# 2014_PDU_REV-7_2_2.net
KiCad netlist of a schematic drawn in EAGLE
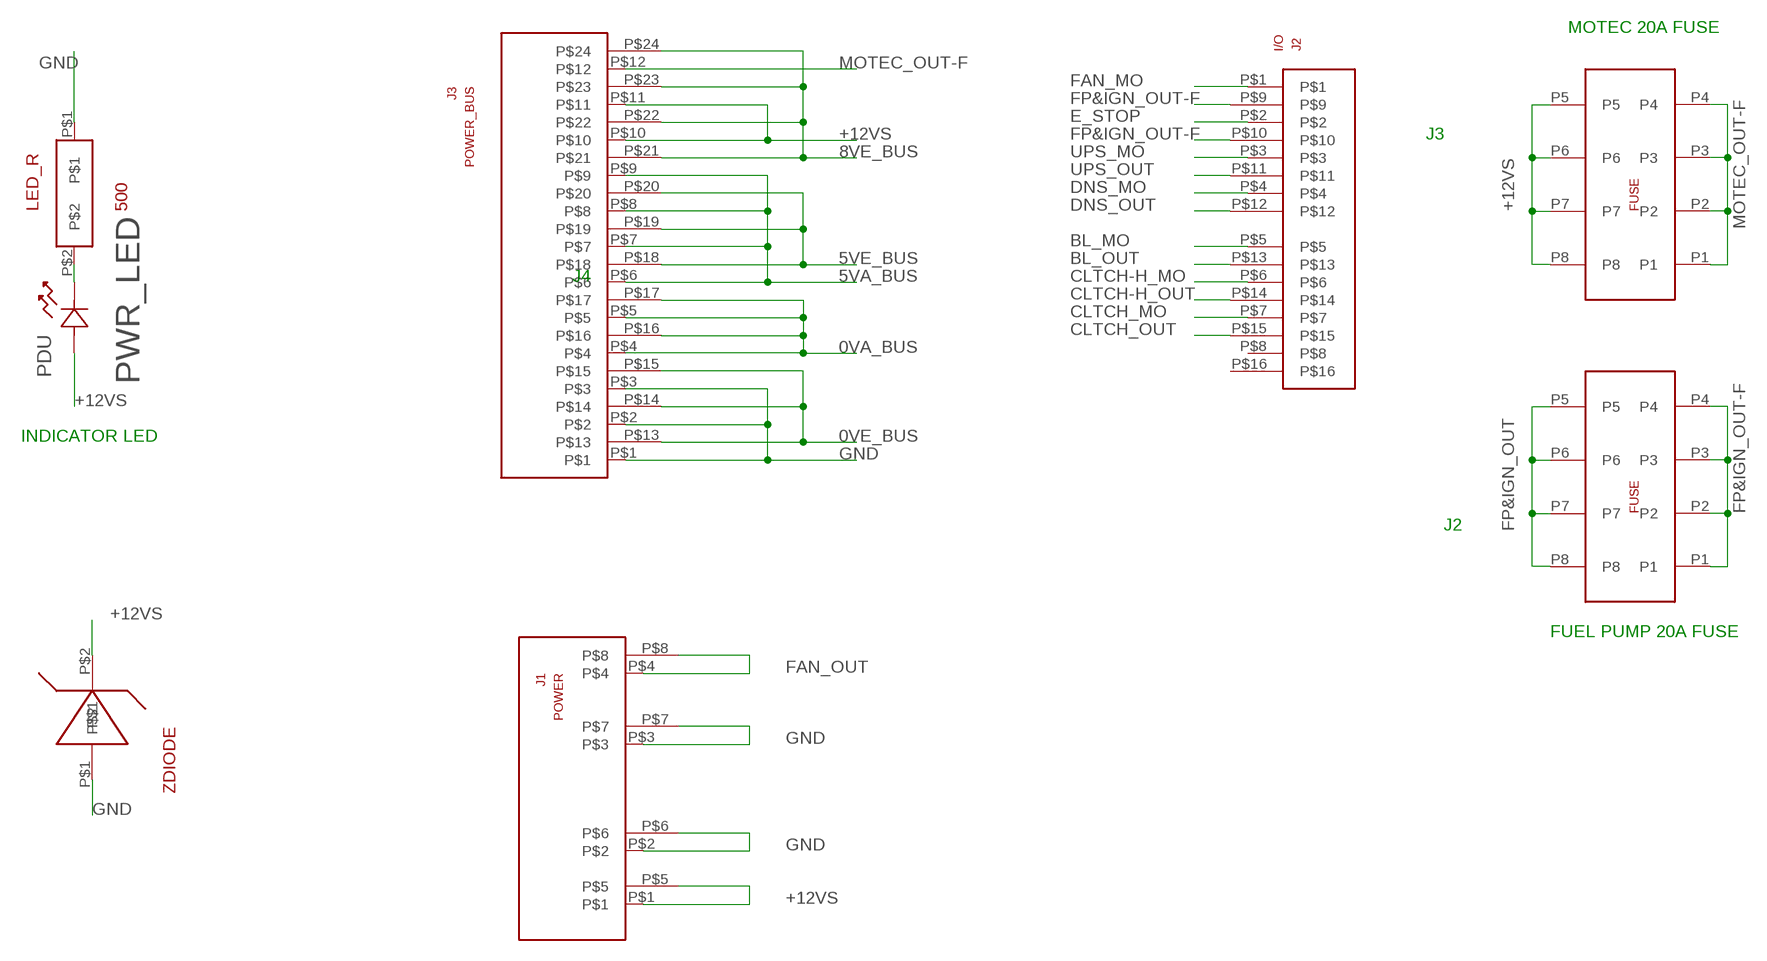
[diagram p0: schematic, sheet 1]
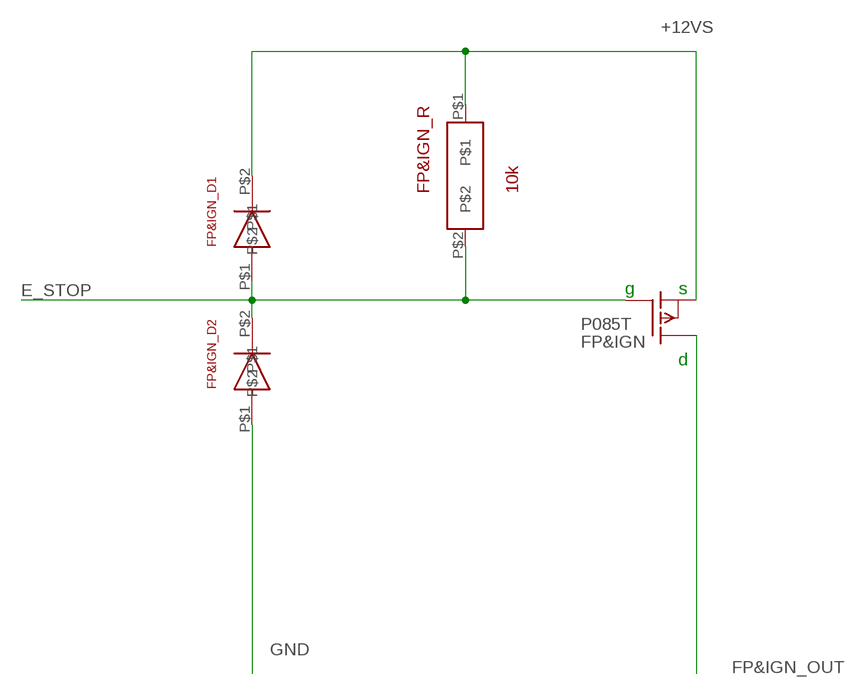
[diagram p1: schematic, sheet 2]
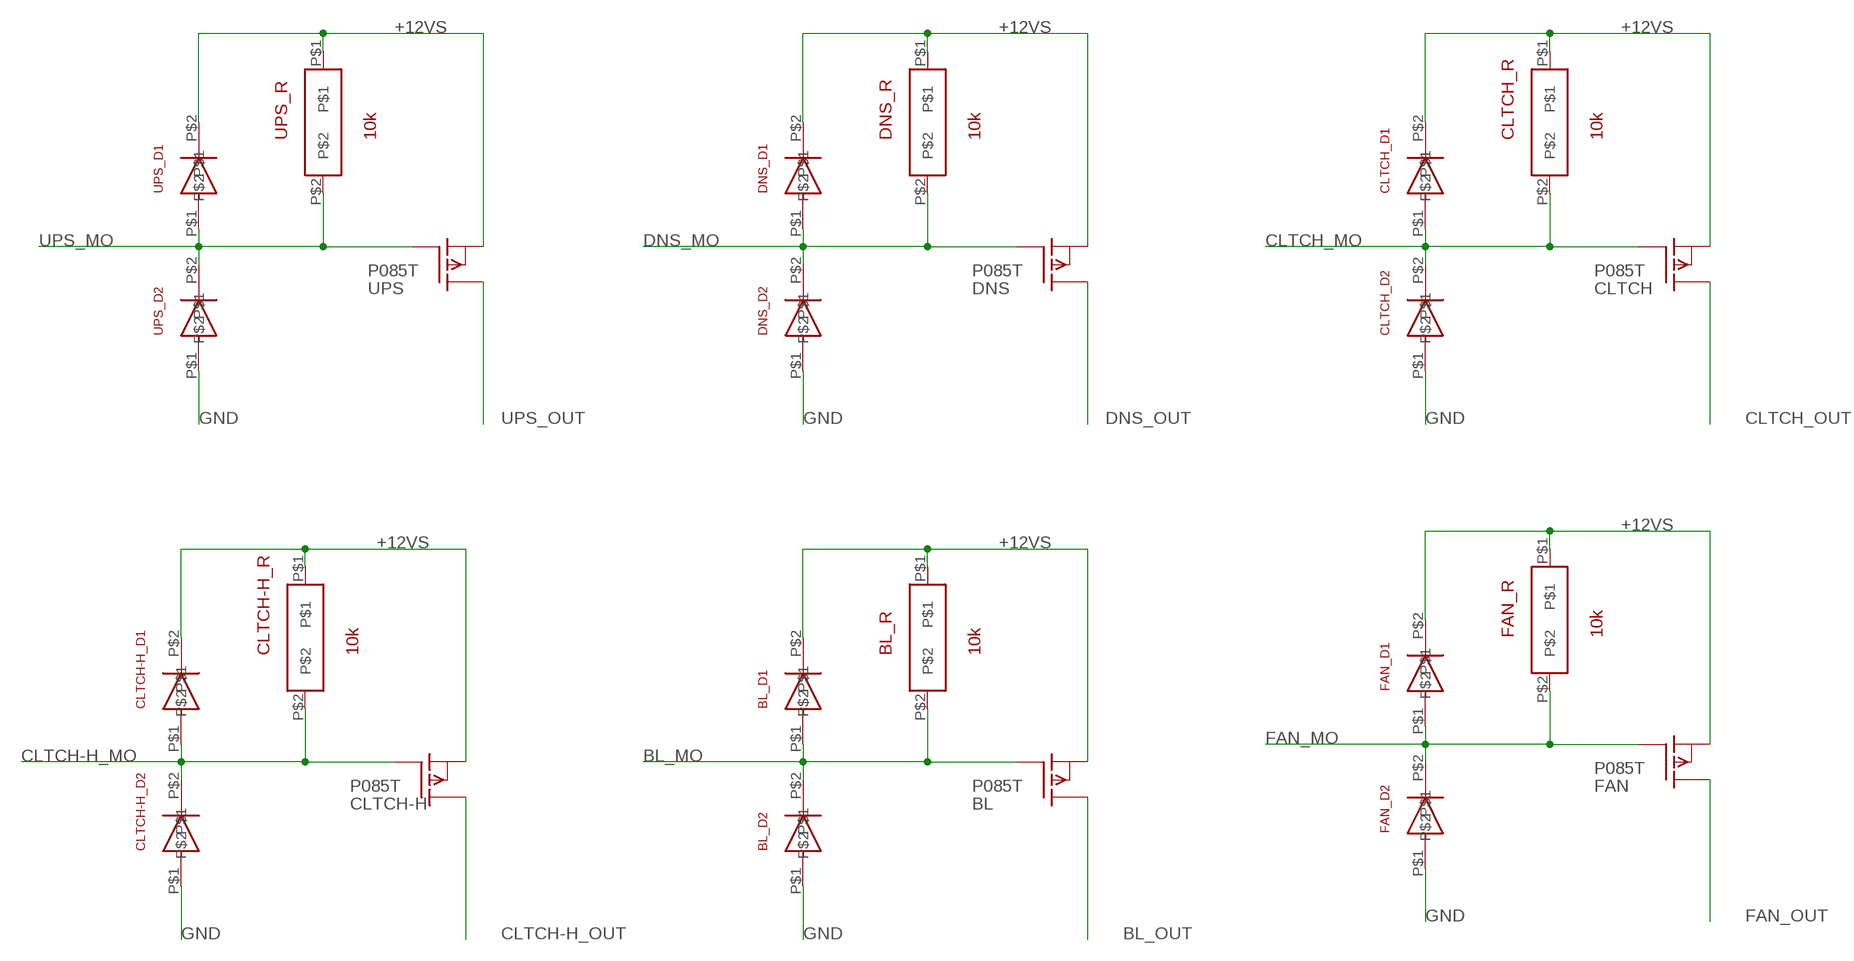
[diagram p2: schematic, sheet 3]

(export (version "E")
  (design (tool "Eeschema 10.0.6"))
  (components
    (comp (ref "FP&IGN")
      (value "P085T")
      (footprint "eagle-import:TO220")
      (libsource (lib "eagle-import") (part "BUZ172"))
    )
    (comp (ref "FP&IGN_D1")
      (value "ER3JB-TP")
      (footprint "eagle-import:ER3JB-TP")
      (libsource (lib "eagle-import") (part "ER3JB-TP"))
    )
    (comp (ref "FP&IGN_D2")
      (value "ER3JB-TP")
      (footprint "eagle-import:ER3JB-TP")
      (libsource (lib "eagle-import") (part "ER3JB-TP"))
    )
    (comp (ref "FP&IGN_R")
      (value "10k")
      (footprint "eagle-import:CRCW_2010_10K0_JNEF")
      (libsource (lib "eagle-import") (part "CRCW_2010_10K0_JNEF"))
    )
    (comp (ref "BL")
      (value "P085T")
      (footprint "eagle-import:TO220")
      (libsource (lib "eagle-import") (part "BUZ172"))
    )
    (comp (ref "BL_D1")
      (value "ER3JB-TP")
      (footprint "eagle-import:ER3JB-TP")
      (libsource (lib "eagle-import") (part "ER3JB-TP"))
    )
    (comp (ref "BL_D2")
      (value "ER3JB-TP")
      (footprint "eagle-import:ER3JB-TP")
      (libsource (lib "eagle-import") (part "ER3JB-TP"))
    )
    (comp (ref "BL_R")
      (value "10k")
      (footprint "eagle-import:CRCW_2010_10K0_JNEF")
      (libsource (lib "eagle-import") (part "CRCW_2010_10K0_JNEF"))
    )
    (comp (ref "CLTCH")
      (value "P085T")
      (footprint "eagle-import:TO220")
      (libsource (lib "eagle-import") (part "BUZ172"))
    )
    (comp (ref "CLTCH-H")
      (value "P085T")
      (footprint "eagle-import:TO220")
      (libsource (lib "eagle-import") (part "BUZ172"))
    )
    (comp (ref "CLTCH-H_D1")
      (value "ER3JB-TP")
      (footprint "eagle-import:ER3JB-TP")
      (libsource (lib "eagle-import") (part "ER3JB-TP"))
    )
    (comp (ref "CLTCH-H_D2")
      (value "ER3JB-TP")
      (footprint "eagle-import:ER3JB-TP")
      (libsource (lib "eagle-import") (part "ER3JB-TP"))
    )
    (comp (ref "CLTCH-H_R")
      (value "10k")
      (footprint "eagle-import:CRCW_2010_10K0_JNEF")
      (libsource (lib "eagle-import") (part "CRCW_2010_10K0_JNEF"))
    )
    (comp (ref "CLTCH_D1")
      (value "ER3JB-TP")
      (footprint "eagle-import:ER3JB-TP")
      (libsource (lib "eagle-import") (part "ER3JB-TP"))
    )
    (comp (ref "CLTCH_D2")
      (value "ER3JB-TP")
      (footprint "eagle-import:ER3JB-TP")
      (libsource (lib "eagle-import") (part "ER3JB-TP"))
    )
    (comp (ref "CLTCH_R")
      (value "10k")
      (footprint "eagle-import:CRCW_2010_10K0_JNEF")
      (libsource (lib "eagle-import") (part "CRCW_2010_10K0_JNEF"))
    )
    (comp (ref "DNS")
      (value "P085T")
      (footprint "eagle-import:TO220")
      (libsource (lib "eagle-import") (part "BUZ172"))
    )
    (comp (ref "DNS_D1")
      (value "ER3JB-TP")
      (footprint "eagle-import:ER3JB-TP")
      (libsource (lib "eagle-import") (part "ER3JB-TP"))
    )
    (comp (ref "DNS_D2")
      (value "ER3JB-TP")
      (footprint "eagle-import:ER3JB-TP")
      (libsource (lib "eagle-import") (part "ER3JB-TP"))
    )
    (comp (ref "DNS_R")
      (value "10k")
      (footprint "eagle-import:CRCW_2010_10K0_JNEF")
      (libsource (lib "eagle-import") (part "CRCW_2010_10K0_JNEF"))
    )
    (comp (ref "FAN")
      (value "P085T")
      (footprint "eagle-import:TO220")
      (libsource (lib "eagle-import") (part "BUZ172"))
    )
    (comp (ref "FAN_D1")
      (value "ER3JB-TP")
      (footprint "eagle-import:ER3JB-TP")
      (libsource (lib "eagle-import") (part "ER3JB-TP"))
    )
    (comp (ref "FAN_D2")
      (value "ER3JB-TP")
      (footprint "eagle-import:ER3JB-TP")
      (libsource (lib "eagle-import") (part "ER3JB-TP"))
    )
    (comp (ref "FAN_R")
      (value "10k")
      (footprint "eagle-import:CRCW_2010_10K0_JNEF")
      (libsource (lib "eagle-import") (part "CRCW_2010_10K0_JNEF"))
    )
    (comp (ref "UPS")
      (value "P085T")
      (footprint "eagle-import:TO220")
      (libsource (lib "eagle-import") (part "BUZ172"))
    )
    (comp (ref "UPS_D1")
      (value "ER3JB-TP")
      (footprint "eagle-import:ER3JB-TP")
      (libsource (lib "eagle-import") (part "ER3JB-TP"))
    )
    (comp (ref "UPS_D2")
      (value "ER3JB-TP")
      (footprint "eagle-import:ER3JB-TP")
      (libsource (lib "eagle-import") (part "ER3JB-TP"))
    )
    (comp (ref "UPS_R")
      (value "10k")
      (footprint "eagle-import:CRCW_2010_10K0_JNEF")
      (libsource (lib "eagle-import") (part "CRCW_2010_10K0_JNEF"))
    )
    (comp (ref "I/O")
      (value "J2")
      (footprint "eagle-import:39-30-1160")
      (libsource (lib "eagle-import") (part "39-30-1160"))
    )
    (comp (ref "LED_R")
      (value "500")
      (footprint "eagle-import:CRCW_2010_390R_JNEF")
      (libsource (lib "eagle-import") (part "CRCW_2010_390R_JNEF"))
    )
    (comp (ref "PDU")
      (value "PWR_LED")
      (footprint "eagle-import:LED_597-3111-407F")
      (fields (field (name "MPN") "597-3111-407F"))
      (libsource (lib "eagle-import") (part "597-3111-407F"))
    )
    (comp (ref "POWER")
      (value "J1")
      (footprint "eagle-import:42820-4223")
      (libsource (lib "eagle-import") (part "42820-4223"))
    )
    (comp (ref "POWER_BUS")
      (value "J3")
      (footprint "eagle-import:39-30-1240")
      (libsource (lib "eagle-import") (part "39-30-1240"))
    )
    (comp (ref "U$1")
      (value "178.6165.0002")
      (footprint "eagle-import:178.6165.0002")
      (libsource (lib "eagle-import") (part "178.6165.0002"))
    )
    (comp (ref "U$2")
      (value "178.6165.0002")
      (footprint "eagle-import:178.6165.0002")
      (libsource (lib "eagle-import") (part "178.6165.0002"))
    )
    (comp (ref "ZDIODE")
      (value "DDZ20C-7")
      (footprint "eagle-import:DDZ20C-7")
      (libsource (lib "eagle-import") (part "DDZ20C-7"))
    )
  )
  (nets
    (net (code "1") (name "+12VS") (class "Default")
      (node (ref "BL") (pin "3") (pinfunction "S_3") (pintype "passive"))
      (node (ref "BL_D1") (pin "P$2") (pinfunction "P$2_P$2") (pintype "bidirectional"))
      (node (ref "BL_R") (pin "P$1") (pinfunction "P$1_P$1") (pintype "bidirectional"))
      (node (ref "CLTCH") (pin "3") (pinfunction "S_3") (pintype "passive"))
      (node (ref "CLTCH-H") (pin "3") (pinfunction "S_3") (pintype "passive"))
      (node (ref "CLTCH-H_D1") (pin "P$2") (pinfunction "P$2_P$2") (pintype "bidirectional"))
      (node (ref "CLTCH-H_R") (pin "P$1") (pinfunction "P$1_P$1") (pintype "bidirectional"))
      (node (ref "CLTCH_D1") (pin "P$2") (pinfunction "P$2_P$2") (pintype "bidirectional"))
      (node (ref "CLTCH_R") (pin "P$1") (pinfunction "P$1_P$1") (pintype "bidirectional"))
      (node (ref "DNS") (pin "3") (pinfunction "S_3") (pintype "passive"))
      (node (ref "DNS_D1") (pin "P$2") (pinfunction "P$2_P$2") (pintype "bidirectional"))
      (node (ref "DNS_R") (pin "P$1") (pinfunction "P$1_P$1") (pintype "bidirectional"))
      (node (ref "FAN") (pin "3") (pinfunction "S_3") (pintype "passive"))
      (node (ref "FAN_D1") (pin "P$2") (pinfunction "P$2_P$2") (pintype "bidirectional"))
      (node (ref "FAN_R") (pin "P$1") (pinfunction "P$1_P$1") (pintype "bidirectional"))
      (node (ref "FP&IGN") (pin "3") (pinfunction "S_3") (pintype "passive"))
      (node (ref "FP&IGN_D1") (pin "P$2") (pinfunction "P$2_P$2") (pintype "bidirectional"))
      (node (ref "FP&IGN_R") (pin "P$1") (pinfunction "P$1_P$1") (pintype "bidirectional"))
      (node (ref "PDU") (pin "2") (pinfunction "2_2") (pintype "passive"))
      (node (ref "POWER") (pin "P$1") (pinfunction "P$1_P$1") (pintype "bidirectional"))
      (node (ref "POWER") (pin "P$5") (pinfunction "P$5_P$5") (pintype "bidirectional"))
      (node (ref "POWER_BUS") (pin "P$10") (pinfunction "P$10_P$10") (pintype "bidirectional"))
      (node (ref "POWER_BUS") (pin "P$11") (pinfunction "P$11_P$11") (pintype "bidirectional"))
      (node (ref "U$1") (pin "P5") (pinfunction "P5_P5") (pintype "bidirectional"))
      (node (ref "U$1") (pin "P6") (pinfunction "P6_P6") (pintype "bidirectional"))
      (node (ref "U$1") (pin "P7") (pinfunction "P7_P7") (pintype "bidirectional"))
      (node (ref "U$1") (pin "P8") (pinfunction "P8_P8") (pintype "bidirectional"))
      (node (ref "UPS") (pin "3") (pinfunction "S_3") (pintype "passive"))
      (node (ref "UPS_D1") (pin "P$2") (pinfunction "P$2_P$2") (pintype "bidirectional"))
      (node (ref "UPS_R") (pin "P$1") (pinfunction "P$1_P$1") (pintype "bidirectional"))
      (node (ref "ZDIODE") (pin "P$2") (pinfunction "P$2_P$2") (pintype "bidirectional"))
    )
    (net (code "2") (name "0VA_BUS") (class "Default")
      (node (ref "POWER_BUS") (pin "P$16") (pinfunction "P$16_P$16") (pintype "bidirectional"))
      (node (ref "POWER_BUS") (pin "P$17") (pinfunction "P$17_P$17") (pintype "bidirectional"))
      (node (ref "POWER_BUS") (pin "P$4") (pinfunction "P$4_P$4") (pintype "bidirectional"))
      (node (ref "POWER_BUS") (pin "P$5") (pinfunction "P$5_P$5") (pintype "bidirectional"))
    )
    (net (code "3") (name "0VE_BUS") (class "Default")
      (node (ref "POWER_BUS") (pin "P$13") (pinfunction "P$13_P$13") (pintype "bidirectional"))
      (node (ref "POWER_BUS") (pin "P$14") (pinfunction "P$14_P$14") (pintype "bidirectional"))
      (node (ref "POWER_BUS") (pin "P$15") (pinfunction "P$15_P$15") (pintype "bidirectional"))
    )
    (net (code "4") (name "5VA_BUS") (class "Default")
      (node (ref "POWER_BUS") (pin "P$6") (pinfunction "P$6_P$6") (pintype "bidirectional"))
      (node (ref "POWER_BUS") (pin "P$7") (pinfunction "P$7_P$7") (pintype "bidirectional"))
      (node (ref "POWER_BUS") (pin "P$8") (pinfunction "P$8_P$8") (pintype "bidirectional"))
      (node (ref "POWER_BUS") (pin "P$9") (pinfunction "P$9_P$9") (pintype "bidirectional"))
    )
    (net (code "5") (name "5VE_BUS") (class "Default")
      (node (ref "POWER_BUS") (pin "P$18") (pinfunction "P$18_P$18") (pintype "bidirectional"))
      (node (ref "POWER_BUS") (pin "P$19") (pinfunction "P$19_P$19") (pintype "bidirectional"))
      (node (ref "POWER_BUS") (pin "P$20") (pinfunction "P$20_P$20") (pintype "bidirectional"))
    )
    (net (code "6") (name "8VE_BUS") (class "Default")
      (node (ref "POWER_BUS") (pin "P$21") (pinfunction "P$21_P$21") (pintype "bidirectional"))
      (node (ref "POWER_BUS") (pin "P$22") (pinfunction "P$22_P$22") (pintype "bidirectional"))
      (node (ref "POWER_BUS") (pin "P$23") (pinfunction "P$23_P$23") (pintype "bidirectional"))
      (node (ref "POWER_BUS") (pin "P$24") (pinfunction "P$24_P$24") (pintype "bidirectional"))
    )
    (net (code "7") (name "BL_MO") (class "Default")
      (node (ref "BL") (pin "1") (pinfunction "G_1") (pintype "passive"))
      (node (ref "BL_D1") (pin "P$1") (pinfunction "P$1_P$1") (pintype "bidirectional"))
      (node (ref "BL_D2") (pin "P$2") (pinfunction "P$2_P$2") (pintype "bidirectional"))
      (node (ref "BL_R") (pin "P$2") (pinfunction "P$2_P$2") (pintype "bidirectional"))
      (node (ref "I/O") (pin "P$5") (pinfunction "P$5_P$5") (pintype "bidirectional"))
    )
    (net (code "8") (name "BL_OUT") (class "Default")
      (node (ref "BL") (pin "2") (pinfunction "D_2") (pintype "passive"))
      (node (ref "I/O") (pin "P$13") (pinfunction "P$13_P$13") (pintype "bidirectional"))
    )
    (net (code "9") (name "CLTCH-H_MO") (class "Default")
      (node (ref "CLTCH-H") (pin "1") (pinfunction "G_1") (pintype "passive"))
      (node (ref "CLTCH-H_D1") (pin "P$1") (pinfunction "P$1_P$1") (pintype "bidirectional"))
      (node (ref "CLTCH-H_D2") (pin "P$2") (pinfunction "P$2_P$2") (pintype "bidirectional"))
      (node (ref "CLTCH-H_R") (pin "P$2") (pinfunction "P$2_P$2") (pintype "bidirectional"))
      (node (ref "I/O") (pin "P$6") (pinfunction "P$6_P$6") (pintype "bidirectional"))
    )
    (net (code "10") (name "CLTCH-H_OUT") (class "Default")
      (node (ref "CLTCH-H") (pin "2") (pinfunction "D_2") (pintype "passive"))
      (node (ref "I/O") (pin "P$14") (pinfunction "P$14_P$14") (pintype "bidirectional"))
    )
    (net (code "11") (name "CLTCH_MO") (class "Default")
      (node (ref "CLTCH") (pin "1") (pinfunction "G_1") (pintype "passive"))
      (node (ref "CLTCH_D1") (pin "P$1") (pinfunction "P$1_P$1") (pintype "bidirectional"))
      (node (ref "CLTCH_D2") (pin "P$2") (pinfunction "P$2_P$2") (pintype "bidirectional"))
      (node (ref "CLTCH_R") (pin "P$2") (pinfunction "P$2_P$2") (pintype "bidirectional"))
      (node (ref "I/O") (pin "P$7") (pinfunction "P$7_P$7") (pintype "bidirectional"))
    )
    (net (code "12") (name "CLTCH_OUT") (class "Default")
      (node (ref "CLTCH") (pin "2") (pinfunction "D_2") (pintype "passive"))
      (node (ref "I/O") (pin "P$15") (pinfunction "P$15_P$15") (pintype "bidirectional"))
    )
    (net (code "13") (name "DNS_MO") (class "Default")
      (node (ref "DNS") (pin "1") (pinfunction "G_1") (pintype "passive"))
      (node (ref "DNS_D1") (pin "P$1") (pinfunction "P$1_P$1") (pintype "bidirectional"))
      (node (ref "DNS_D2") (pin "P$2") (pinfunction "P$2_P$2") (pintype "bidirectional"))
      (node (ref "DNS_R") (pin "P$2") (pinfunction "P$2_P$2") (pintype "bidirectional"))
      (node (ref "I/O") (pin "P$4") (pinfunction "P$4_P$4") (pintype "bidirectional"))
    )
    (net (code "14") (name "DNS_OUT") (class "Default")
      (node (ref "DNS") (pin "2") (pinfunction "D_2") (pintype "passive"))
      (node (ref "I/O") (pin "P$12") (pinfunction "P$12_P$12") (pintype "bidirectional"))
    )
    (net (code "15") (name "E_STOP") (class "Default")
      (node (ref "FP&IGN") (pin "1") (pinfunction "G_1") (pintype "passive"))
      (node (ref "FP&IGN_D1") (pin "P$1") (pinfunction "P$1_P$1") (pintype "bidirectional"))
      (node (ref "FP&IGN_D2") (pin "P$2") (pinfunction "P$2_P$2") (pintype "bidirectional"))
      (node (ref "FP&IGN_R") (pin "P$2") (pinfunction "P$2_P$2") (pintype "bidirectional"))
      (node (ref "I/O") (pin "P$2") (pinfunction "P$2_P$2") (pintype "bidirectional"))
    )
    (net (code "16") (name "FAN_MO") (class "Default")
      (node (ref "FAN") (pin "1") (pinfunction "G_1") (pintype "passive"))
      (node (ref "FAN_D1") (pin "P$1") (pinfunction "P$1_P$1") (pintype "bidirectional"))
      (node (ref "FAN_D2") (pin "P$2") (pinfunction "P$2_P$2") (pintype "bidirectional"))
      (node (ref "FAN_R") (pin "P$2") (pinfunction "P$2_P$2") (pintype "bidirectional"))
      (node (ref "I/O") (pin "P$1") (pinfunction "P$1_P$1") (pintype "bidirectional"))
    )
    (net (code "17") (name "FAN_OUT") (class "Default")
      (node (ref "FAN") (pin "2") (pinfunction "D_2") (pintype "passive"))
      (node (ref "POWER") (pin "P$4") (pinfunction "P$4_P$4") (pintype "bidirectional"))
      (node (ref "POWER") (pin "P$8") (pinfunction "P$8_P$8") (pintype "bidirectional"))
    )
    (net (code "18") (name "FP&IGN_OUT") (class "Default")
      (node (ref "FP&IGN") (pin "2") (pinfunction "D_2") (pintype "passive"))
      (node (ref "U$2") (pin "P5") (pinfunction "P5_P5") (pintype "bidirectional"))
      (node (ref "U$2") (pin "P6") (pinfunction "P6_P6") (pintype "bidirectional"))
      (node (ref "U$2") (pin "P7") (pinfunction "P7_P7") (pintype "bidirectional"))
      (node (ref "U$2") (pin "P8") (pinfunction "P8_P8") (pintype "bidirectional"))
    )
    (net (code "19") (name "FP&IGN_OUT-F") (class "Default")
      (node (ref "I/O") (pin "P$10") (pinfunction "P$10_P$10") (pintype "bidirectional"))
      (node (ref "I/O") (pin "P$9") (pinfunction "P$9_P$9") (pintype "bidirectional"))
      (node (ref "U$2") (pin "P1") (pinfunction "P1_P1") (pintype "bidirectional"))
      (node (ref "U$2") (pin "P2") (pinfunction "P2_P2") (pintype "bidirectional"))
      (node (ref "U$2") (pin "P3") (pinfunction "P3_P3") (pintype "bidirectional"))
      (node (ref "U$2") (pin "P4") (pinfunction "P4_P4") (pintype "bidirectional"))
    )
    (net (code "20") (name "GND") (class "Default")
      (node (ref "BL_D2") (pin "P$1") (pinfunction "P$1_P$1") (pintype "bidirectional"))
      (node (ref "CLTCH-H_D2") (pin "P$1") (pinfunction "P$1_P$1") (pintype "bidirectional"))
      (node (ref "CLTCH_D2") (pin "P$1") (pinfunction "P$1_P$1") (pintype "bidirectional"))
      (node (ref "DNS_D2") (pin "P$1") (pinfunction "P$1_P$1") (pintype "bidirectional"))
      (node (ref "FAN_D2") (pin "P$1") (pinfunction "P$1_P$1") (pintype "bidirectional"))
      (node (ref "FP&IGN_D2") (pin "P$1") (pinfunction "P$1_P$1") (pintype "bidirectional"))
      (node (ref "LED_R") (pin "P$1") (pinfunction "P$1_P$1") (pintype "bidirectional"))
      (node (ref "POWER") (pin "P$2") (pinfunction "P$2_P$2") (pintype "bidirectional"))
      (node (ref "POWER") (pin "P$3") (pinfunction "P$3_P$3") (pintype "bidirectional"))
      (node (ref "POWER") (pin "P$6") (pinfunction "P$6_P$6") (pintype "bidirectional"))
      (node (ref "POWER") (pin "P$7") (pinfunction "P$7_P$7") (pintype "bidirectional"))
      (node (ref "POWER_BUS") (pin "P$1") (pinfunction "P$1_P$1") (pintype "bidirectional"))
      (node (ref "POWER_BUS") (pin "P$2") (pinfunction "P$2_P$2") (pintype "bidirectional"))
      (node (ref "POWER_BUS") (pin "P$3") (pinfunction "P$3_P$3") (pintype "bidirectional"))
      (node (ref "UPS_D2") (pin "P$1") (pinfunction "P$1_P$1") (pintype "bidirectional"))
      (node (ref "ZDIODE") (pin "P$1") (pinfunction "P$1_P$1") (pintype "bidirectional"))
    )
    (net (code "21") (name "MOTEC_OUT-F") (class "Default")
      (node (ref "POWER_BUS") (pin "P$12") (pinfunction "P$12_P$12") (pintype "bidirectional"))
      (node (ref "U$1") (pin "P1") (pinfunction "P1_P1") (pintype "bidirectional"))
      (node (ref "U$1") (pin "P2") (pinfunction "P2_P2") (pintype "bidirectional"))
      (node (ref "U$1") (pin "P3") (pinfunction "P3_P3") (pintype "bidirectional"))
      (node (ref "U$1") (pin "P4") (pinfunction "P4_P4") (pintype "bidirectional"))
    )
    (net (code "22") (name "Net-(LED_R-PadP$2)") (class "Default")
      (node (ref "LED_R") (pin "P$2") (pinfunction "P$2_P$2") (pintype "bidirectional"))
      (node (ref "PDU") (pin "1") (pinfunction "1_1") (pintype "passive"))
    )
    (net (code "23") (name "UPS_MO") (class "Default")
      (node (ref "I/O") (pin "P$3") (pinfunction "P$3_P$3") (pintype "bidirectional"))
      (node (ref "UPS") (pin "1") (pinfunction "G_1") (pintype "passive"))
      (node (ref "UPS_D1") (pin "P$1") (pinfunction "P$1_P$1") (pintype "bidirectional"))
      (node (ref "UPS_D2") (pin "P$2") (pinfunction "P$2_P$2") (pintype "bidirectional"))
      (node (ref "UPS_R") (pin "P$2") (pinfunction "P$2_P$2") (pintype "bidirectional"))
    )
    (net (code "24") (name "UPS_OUT") (class "Default")
      (node (ref "I/O") (pin "P$11") (pinfunction "P$11_P$11") (pintype "bidirectional"))
      (node (ref "UPS") (pin "2") (pinfunction "D_2") (pintype "passive"))
    )
    (net (code "25") (name "unconnected-(I/O-PadP$8)") (class "Default")
      (node (ref "I/O") (pin "P$8") (pinfunction "P$8_P$8") (pintype "bidirectional"))
    )
    (net (code "26") (name "unconnected-(I/O-PadP$16)") (class "Default")
      (node (ref "I/O") (pin "P$16") (pinfunction "P$16_P$16") (pintype "bidirectional"))
    )
  )
)
